# HV_Detect.net
KiCad netlist of a schematic drawn in Altium Designer
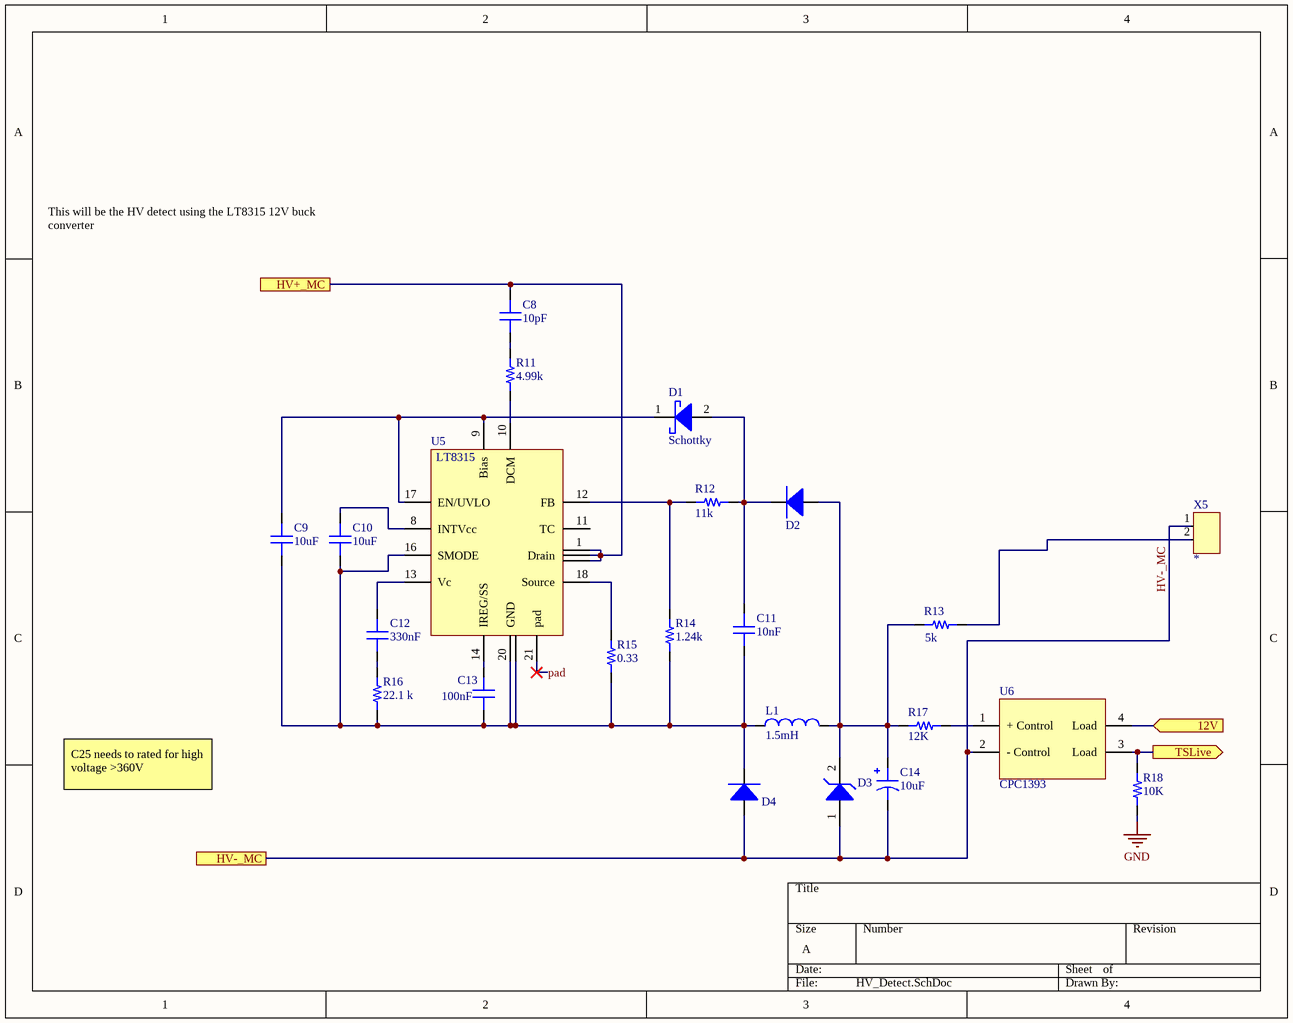
[diagram p0: HV_Detect.SchDoc]

(export (version "E")
  (design (tool "Eeschema 10.0.6"))
  (components
    (comp (ref "C8")
      (value "~")
      (footprint "CAP 0805/2012")
      (description "10pF 500V Ceramic 0805")
      (fields
        (field (name "CAPACITANCE") "10pF")
        (field (name "VOLTAGE") "500")
        (field (name "CREATEDBY") "Eric Tse")
        (field (name "UPDATEDBY") "Eric Tse")
      )
      (libsource (lib "altlib") (part "Capacitor"))
    )
    (comp (ref "C9")
      (value "capacitor")
      (footprint "0603")
      (description "Generic 0603 capacitor")
      (fields (field (name "CAPACITANCE") "10uF") (field (name "VOLTAGE") "50"))
      (libsource (lib "altlib") (part "capacitor"))
    )
    (comp (ref "C10")
      (value "capacitor")
      (footprint "0603")
      (description "Generic 0603 capacitor")
      (fields (field (name "CAPACITANCE") "10uF") (field (name "VOLTAGE") "50"))
      (libsource (lib "altlib") (part "capacitor"))
    )
    (comp (ref "C11")
      (value "capacitor")
      (footprint "0603")
      (description "Generic 0603 capacitor")
      (fields (field (name "CAPACITANCE") "10nF") (field (name "VOLTAGE") "50"))
      (libsource (lib "altlib") (part "capacitor"))
    )
    (comp (ref "C12")
      (value "capacitor")
      (footprint "0603")
      (description "Generic 0603 capacitor")
      (fields (field (name "CAPACITANCE") "330nF") (field (name "VOLTAGE") "50"))
      (libsource (lib "altlib") (part "capacitor"))
    )
    (comp (ref "C13")
      (value "capacitor")
      (footprint "0603")
      (description "Generic 0603 capacitor")
      (fields (field (name "CAPACITANCE") "100nF") (field (name "VOLTAGE") "50"))
      (libsource (lib "altlib") (part "capacitor"))
    )
    (comp (ref "C14")
      (value "Capacitor_Electrolytic")
      (footprint "CMMR1U-06")
      (description "10µF 400V Aluminum Electrolytic Capacitors Ra")
      (fields (field (name "CAPACITANCE") "10uF") (field (name "VOLTAGE") "400"))
      (libsource (lib "altlib") (part "Capacitor_Electrolytic"))
    )
    (comp (ref "D1")
      (value "Schottky")
      (footprint "SOD323")
      (description "30V 200mA schottky diode")
      (fields (field (name "CREATEDBY") "Eric Tse") (field (name "UPDATEDBY") "Eric Tse"))
      (libsource (lib "altlib") (part "Schottky"))
    )
    (comp (ref "D2")
      (value "diode")
      (footprint "CMMR1U-06")
      (description "Diode Standard 600V 1A Surface Mount SOD-123F")
      (libsource (lib "altlib") (part "diode"))
    )
    (comp (ref "D3")
      (value "*")
      (footprint "SOD123F")
      (description "Zener Diode 14V 500mW ±5% Surface Mount SOD-1")
      (libsource (lib "altlib") (part "Zener"))
    )
    (comp (ref "D4")
      (value "diode")
      (footprint "C3D1P7060Q")
      (description "Diode Silicon Carbide Schottky 600V 9.7A (DC)")
      (libsource (lib "altlib") (part "diode"))
    )
    (comp (ref "L1")
      (value "1.5mH")
      (footprint "SDR1005")
      (description "1.5mH inductor")
      (fields
        (field (name "TOLERANCE") "10")
        (field (name "CREATEDBY") "Marc Wong")
        (field (name "UPDATEDBY") "Marc Wong")
      )
      (libsource (lib "altlib") (part "Inductor"))
    )
    (comp (ref "R11")
      (value "4.99k")
      (footprint "RES 0603/1608")
      (fields (field (name "RESISTANCE") "4.99k"))
      (libsource (lib "altlib") (part "Resistor"))
    )
    (comp (ref "R12")
      (value "11k")
      (footprint "RES 0603/1608")
      (fields (field (name "RESISTANCE") "11k"))
      (libsource (lib "altlib") (part "Resistor"))
    )
    (comp (ref "R13")
      (value "5k")
      (footprint "RES 0603/1608")
      (fields (field (name "RESISTANCE") "5k"))
      (libsource (lib "altlib") (part "Resistor"))
    )
    (comp (ref "R14")
      (value "1.24k")
      (footprint "RES 0603/1608")
      (fields (field (name "RESISTANCE") "1.24k"))
      (libsource (lib "altlib") (part "Resistor"))
    )
    (comp (ref "R15")
      (value "0.33")
      (footprint "RES 0603/1608")
      (fields (field (name "RESISTANCE") "0.33"))
      (libsource (lib "altlib") (part "Resistor"))
    )
    (comp (ref "R16")
      (value "22.1 k")
      (footprint "RES 0603/1608")
      (fields (field (name "RESISTANCE") "22.1 k"))
      (libsource (lib "altlib") (part "Resistor"))
    )
    (comp (ref "R17")
      (value "12K")
      (footprint "RES 0603/1608")
      (fields (field (name "RESISTANCE") "12K"))
      (libsource (lib "altlib") (part "Resistor"))
    )
    (comp (ref "R18")
      (value "10K")
      (footprint "RES 0603/1608")
      (fields (field (name "RESISTANCE") "10K"))
      (libsource (lib "altlib") (part "Resistor"))
    )
    (comp (ref "U5")
      (value "LT8315")
      (footprint "TSSOP20-Thermal")
      (description "560Vin - 12Vout Buck Converter")
      (fields (field (name "CREATEDBY") "Eric Tse") (field (name "UPDATEDBY") "Eric Tse"))
      (libsource (lib "altlib") (part "LT8315"))
    )
    (comp (ref "U6")
      (value "CPC1393")
      (footprint "CPC1393GR")
      (description "Solid State Relay SPST-NO (1 Form A) 4-SMD (0.300\", 7.62mm)")
      (fields
        (field (name "MFRPARTNO") "CPC1393GRTR")
        (field (name "CREATED_BY") "Lynette")
        (field (name "UPDATED_BY") "Null")
      )
      (libsource (lib "Altium-Lib") (part "CPC1393"))
    )
    (comp (ref "X5")
      (value "*")
      (footprint "CONN 43650-0200 MOLEX 2PIN")
      (description "Molex 43650_0200")
      (libsource (lib "altlib") (part "CONN 2POS"))
    )
  )
  (nets
    (net (code "1") (name "/12V") (class "Default")
      (node (ref "U6") (pin "4") (pinfunction "Load_4") (pintype "passive"))
    )
    (net (code "2") (name "/HV+_MC") (class "Default")
      (node (ref "C8") (pin "2") (pinfunction "2_2") (pintype "passive"))
      (node (ref "U5") (pin "1") (pinfunction "Drain_1") (pintype "passive"))
      (node (ref "U5") (pin "2") (pinfunction "Drain_2") (pintype "passive"))
      (node (ref "U5") (pin "3") (pinfunction "Drain_3") (pintype "passive"))
    )
    (net (code "3") (name "/HV-_MC") (class "Default")
      (node (ref "C14") (pin "2") (pinfunction "2_2") (pintype "passive"))
      (node (ref "D3") (pin "1") (pinfunction "A_1") (pintype "passive"))
      (node (ref "D4") (pin "2") (pintype "passive"))
      (node (ref "U6") (pin "2") (pinfunction "-_Control_2") (pintype "passive"))
      (node (ref "X5") (pin "1") (pintype "passive"))
    )
    (net (code "4") (name "/TSLive") (class "Default")
      (node (ref "R18") (pin "2") (pinfunction "2_2") (pintype "passive"))
      (node (ref "U6") (pin "3") (pinfunction "Load_3") (pintype "passive"))
    )
    (net (code "5") (name "/pad") (class "Default")
      (node (ref "U5") (pin "21") (pinfunction "pad_21") (pintype "passive+no_connect"))
    )
    (net (code "6") (name "GND") (class "Default")
      (node (ref "R18") (pin "1") (pinfunction "1_1") (pintype "passive"))
    )
    (net (code "7") (name "Net-(C8-Pad1)") (class "Default")
      (node (ref "C8") (pin "1") (pinfunction "1_1") (pintype "passive"))
      (node (ref "R11") (pin "1") (pinfunction "1_1") (pintype "passive"))
    )
    (net (code "8") (name "Net-(C12-Pad1)") (class "Default")
      (node (ref "C12") (pin "1") (pinfunction "1_1") (pintype "passive"))
      (node (ref "R16") (pin "1") (pinfunction "1_1") (pintype "passive"))
    )
    (net (code "9") (name "Net-(D1-A)") (class "Default")
      (node (ref "C11") (pin "2") (pinfunction "2_2") (pintype "passive"))
      (node (ref "D1") (pin "2") (pinfunction "A_2") (pintype "passive"))
      (node (ref "D2") (pin "1") (pintype "passive"))
      (node (ref "R12") (pin "2") (pinfunction "2_2") (pintype "passive"))
    )
    (net (code "10") (name "Net-(D1-K)") (class "Default")
      (node (ref "C9") (pin "1") (pinfunction "1_1") (pintype "passive"))
      (node (ref "D1") (pin "1") (pinfunction "K_1") (pintype "passive"))
      (node (ref "U5") (pin "17") (pinfunction "EN/UVLO_17") (pintype "passive"))
      (node (ref "U5") (pin "9") (pinfunction "Bias_9") (pintype "passive"))
    )
    (net (code "11") (name "Net-(D3-K)") (class "Default")
      (node (ref "C14") (pin "1") (pinfunction "1_1") (pintype "passive"))
      (node (ref "D2") (pin "2") (pintype "passive"))
      (node (ref "D3") (pin "2") (pinfunction "K_2") (pintype "passive"))
      (node (ref "L1") (pin "2") (pinfunction "2_2") (pintype "passive"))
      (node (ref "R13") (pin "1") (pinfunction "1_1") (pintype "passive"))
      (node (ref "R17") (pin "1") (pinfunction "1_1") (pintype "passive"))
    )
    (net (code "12") (name "Net-(R13-Pad2)") (class "Default")
      (node (ref "R13") (pin "2") (pinfunction "2_2") (pintype "passive"))
      (node (ref "X5") (pin "2") (pintype "passive"))
    )
    (net (code "13") (name "Net-(U5-DCM)") (class "Default")
      (node (ref "R11") (pin "2") (pinfunction "2_2") (pintype "passive"))
      (node (ref "U5") (pin "10") (pinfunction "DCM_10") (pintype "passive"))
    )
    (net (code "14") (name "Net-(U5-FB)") (class "Default")
      (node (ref "R12") (pin "1") (pinfunction "1_1") (pintype "passive"))
      (node (ref "R14") (pin "2") (pinfunction "2_2") (pintype "passive"))
      (node (ref "U5") (pin "12") (pinfunction "FB_12") (pintype "passive"))
    )
    (net (code "15") (name "Net-(U5-INTVcc)") (class "Default")
      (node (ref "C10") (pin "1") (pinfunction "1_1") (pintype "passive"))
      (node (ref "U5") (pin "8") (pinfunction "INTVcc_8") (pintype "passive"))
    )
    (net (code "16") (name "Net-(U5-IREG{slash}SS)") (class "Default")
      (node (ref "C13") (pin "2") (pinfunction "2_2") (pintype "passive"))
      (node (ref "U5") (pin "14") (pinfunction "IREG/SS_14") (pintype "passive"))
    )
    (net (code "17") (name "Net-(U5-SMODE)") (class "Default")
      (node (ref "C10") (pin "2") (pinfunction "2_2") (pintype "passive"))
      (node (ref "C11") (pin "1") (pinfunction "1_1") (pintype "passive"))
      (node (ref "C13") (pin "1") (pinfunction "1_1") (pintype "passive"))
      (node (ref "C9") (pin "2") (pinfunction "2_2") (pintype "passive"))
      (node (ref "D4") (pin "1") (pintype "passive"))
      (node (ref "L1") (pin "1") (pinfunction "1_1") (pintype "passive"))
      (node (ref "R14") (pin "1") (pinfunction "1_1") (pintype "passive"))
      (node (ref "R15") (pin "1") (pinfunction "1_1") (pintype "passive"))
      (node (ref "R16") (pin "2") (pinfunction "2_2") (pintype "passive"))
      (node (ref "U5") (pin "15") (pinfunction "GND_15") (pintype "power_in"))
      (node (ref "U5") (pin "16") (pinfunction "SMODE_16") (pintype "passive"))
      (node (ref "U5") (pin "20") (pinfunction "GND_20") (pintype "power_in"))
    )
    (net (code "18") (name "Net-(U5-Source)") (class "Default")
      (node (ref "R15") (pin "2") (pinfunction "2_2") (pintype "passive"))
      (node (ref "U5") (pin "18") (pinfunction "Source_18") (pintype "passive"))
    )
    (net (code "19") (name "Net-(U5-Vc)") (class "Default")
      (node (ref "C12") (pin "2") (pinfunction "2_2") (pintype "passive"))
      (node (ref "U5") (pin "13") (pinfunction "Vc_13") (pintype "power_in"))
    )
    (net (code "20") (name "Net-(U6-+_Control)") (class "Default")
      (node (ref "R17") (pin "2") (pinfunction "2_2") (pintype "passive"))
      (node (ref "U6") (pin "1") (pinfunction "+_Control_1") (pintype "passive"))
    )
    (net (code "21") (name "unconnected-(U5-TC-Pad11)") (class "Default")
      (node (ref "U5") (pin "11") (pinfunction "TC_11") (pintype "passive"))
    )
  )
)
